# 4_RK3588_GND.net
KiCad netlist of a schematic drawn in Altium Designer
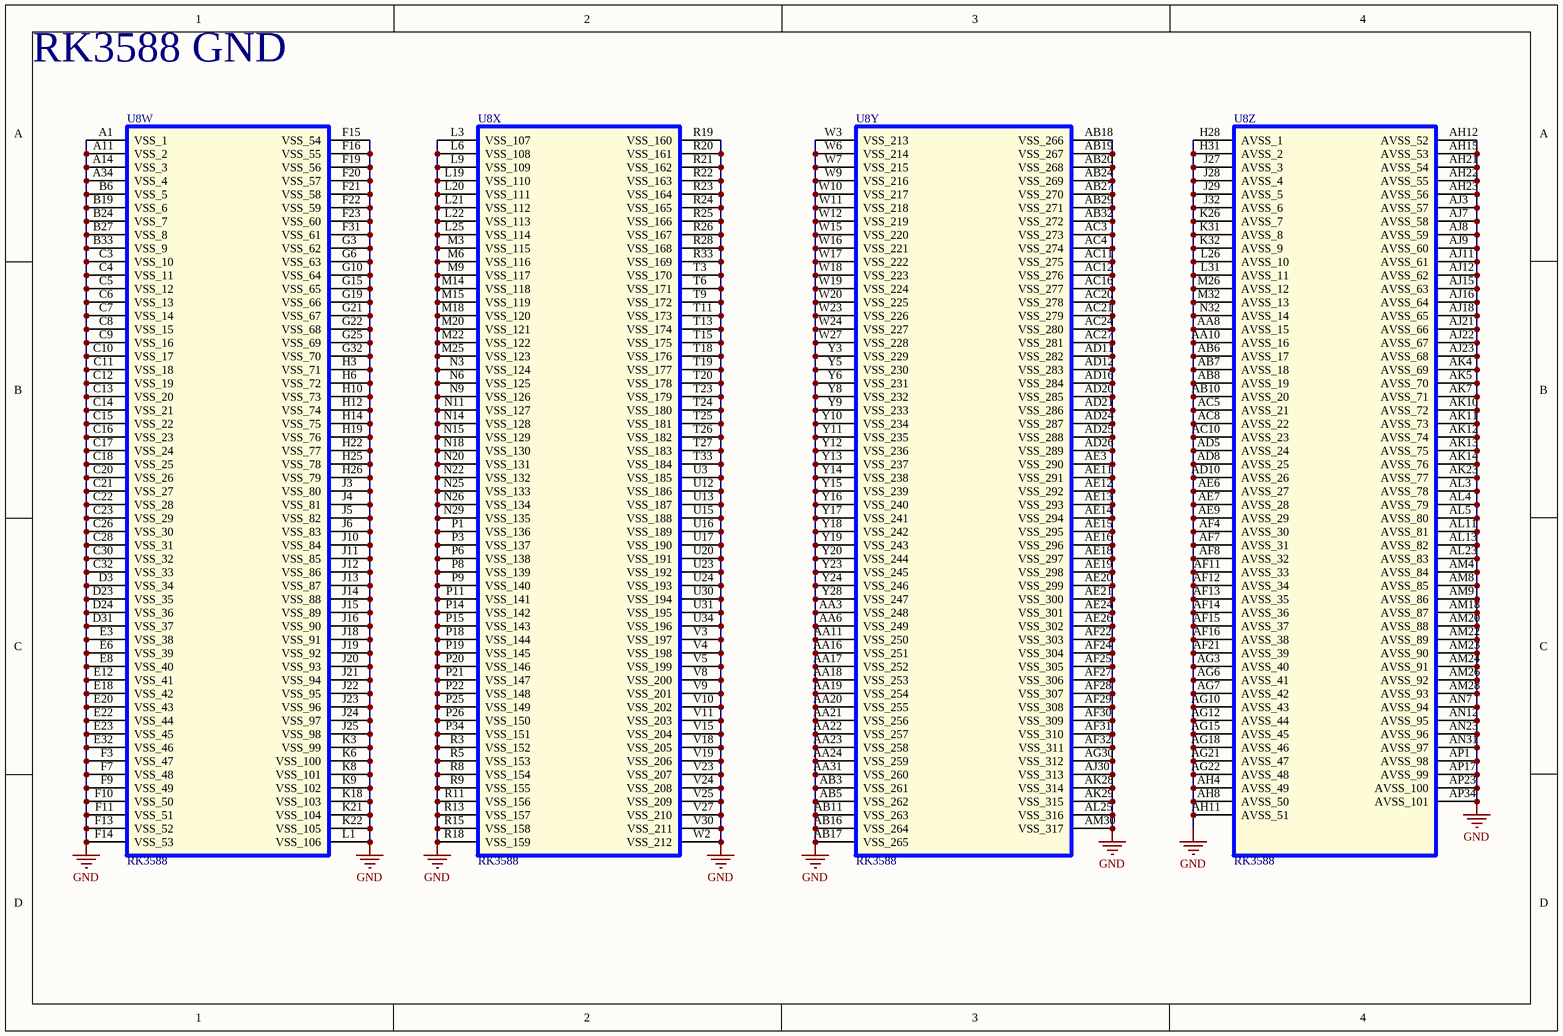
[diagram p0: 4.RK3588_GND.SchDoc]

(export (version "E")
  (design (tool "Eeschema 10.0.6"))
  (components
    (comp (ref "U8")
      (value "RK3588")
      (footprint "0.PCB1:BGA1088_23R00X23R00X2R00")
      (description "ROCKCHIP SOC")
      (libsource (lib "RK3588") (part "SOC_RK3588"))
    )
  )
  (nets
    (net (code "1") (name "GND") (class "Default")
      (node (ref "U8") (pin "A1") (pinfunction "VSS_1_A1") (pintype "power_in"))
      (node (ref "U8") (pin "A11") (pinfunction "VSS_2_A11") (pintype "power_in"))
      (node (ref "U8") (pin "A14") (pinfunction "VSS_3_A14") (pintype "power_in"))
      (node (ref "U8") (pin "A34") (pinfunction "VSS_4_A34") (pintype "power_in"))
      (node (ref "U8") (pin "AA10") (pinfunction "AVSS_16_AA10") (pintype "power_in"))
      (node (ref "U8") (pin "AA11") (pinfunction "VSS_250_AA11") (pintype "power_in"))
      (node (ref "U8") (pin "AA16") (pinfunction "VSS_251_AA16") (pintype "power_in"))
      (node (ref "U8") (pin "AA17") (pinfunction "VSS_252_AA17") (pintype "power_in"))
      (node (ref "U8") (pin "AA18") (pinfunction "VSS_253_AA18") (pintype "power_in"))
      (node (ref "U8") (pin "AA19") (pinfunction "VSS_254_AA19") (pintype "power_in"))
      (node (ref "U8") (pin "AA20") (pinfunction "VSS_255_AA20") (pintype "power_in"))
      (node (ref "U8") (pin "AA21") (pinfunction "VSS_256_AA21") (pintype "power_in"))
      (node (ref "U8") (pin "AA22") (pinfunction "VSS_257_AA22") (pintype "power_in"))
      (node (ref "U8") (pin "AA23") (pinfunction "VSS_258_AA23") (pintype "power_in"))
      (node (ref "U8") (pin "AA24") (pinfunction "VSS_259_AA24") (pintype "power_in"))
      (node (ref "U8") (pin "AA3") (pinfunction "VSS_248_AA3") (pintype "power_in"))
      (node (ref "U8") (pin "AA31") (pinfunction "VSS_260_AA31") (pintype "power_in"))
      (node (ref "U8") (pin "AA6") (pinfunction "VSS_249_AA6") (pintype "power_in"))
      (node (ref "U8") (pin "AA8") (pinfunction "AVSS_15_AA8") (pintype "power_in"))
      (node (ref "U8") (pin "AB10") (pinfunction "AVSS_20_AB10") (pintype "power_in"))
      (node (ref "U8") (pin "AB11") (pinfunction "VSS_263_AB11") (pintype "power_in"))
      (node (ref "U8") (pin "AB16") (pinfunction "VSS_264_AB16") (pintype "power_in"))
      (node (ref "U8") (pin "AB17") (pinfunction "VSS_265_AB17") (pintype "power_in"))
      (node (ref "U8") (pin "AB18") (pinfunction "VSS_266_AB18") (pintype "power_in"))
      (node (ref "U8") (pin "AB19") (pinfunction "VSS_267_AB19") (pintype "power_in"))
      (node (ref "U8") (pin "AB20") (pinfunction "VSS_268_AB20") (pintype "power_in"))
      (node (ref "U8") (pin "AB24") (pinfunction "VSS_269_AB24") (pintype "power_in"))
      (node (ref "U8") (pin "AB27") (pinfunction "VSS_270_AB27") (pintype "power_in"))
      (node (ref "U8") (pin "AB29") (pinfunction "VSS_271_AB29") (pintype "power_in"))
      (node (ref "U8") (pin "AB3") (pinfunction "VSS_261_AB3") (pintype "power_in"))
      (node (ref "U8") (pin "AB32") (pinfunction "VSS_272_AB32") (pintype "power_in"))
      (node (ref "U8") (pin "AB5") (pinfunction "VSS_262_AB5") (pintype "power_in"))
      (node (ref "U8") (pin "AB6") (pinfunction "AVSS_17_AB6") (pintype "power_in"))
      (node (ref "U8") (pin "AB7") (pinfunction "AVSS_18_AB7") (pintype "power_in"))
      (node (ref "U8") (pin "AB8") (pinfunction "AVSS_19_AB8") (pintype "power_in"))
      (node (ref "U8") (pin "AC10") (pinfunction "AVSS_23_AC10") (pintype "power_in"))
      (node (ref "U8") (pin "AC11") (pinfunction "VSS_275_AC11") (pintype "power_in"))
      (node (ref "U8") (pin "AC12") (pinfunction "VSS_276_AC12") (pintype "power_in"))
      (node (ref "U8") (pin "AC16") (pinfunction "VSS_277_AC16") (pintype "power_in"))
      (node (ref "U8") (pin "AC20") (pinfunction "VSS_278_AC20") (pintype "power_in"))
      (node (ref "U8") (pin "AC21") (pinfunction "VSS_279_AC21") (pintype "power_in"))
      (node (ref "U8") (pin "AC24") (pinfunction "VSS_280_AC24") (pintype "power_in"))
      (node (ref "U8") (pin "AC27") (pinfunction "VSS_281_AC27") (pintype "power_in"))
      (node (ref "U8") (pin "AC3") (pinfunction "VSS_273_AC3") (pintype "power_in"))
      (node (ref "U8") (pin "AC4") (pinfunction "VSS_274_AC4") (pintype "power_in"))
      (node (ref "U8") (pin "AC5") (pinfunction "AVSS_21_AC5") (pintype "power_in"))
      (node (ref "U8") (pin "AC8") (pinfunction "AVSS_22_AC8") (pintype "power_in"))
      (node (ref "U8") (pin "AD10") (pinfunction "AVSS_26_AD10") (pintype "power_in"))
      (node (ref "U8") (pin "AD11") (pinfunction "VSS_282_AD11") (pintype "power_in"))
      (node (ref "U8") (pin "AD12") (pinfunction "VSS_283_AD12") (pintype "power_in"))
      (node (ref "U8") (pin "AD16") (pinfunction "VSS_284_AD16") (pintype "power_in"))
      (node (ref "U8") (pin "AD20") (pinfunction "VSS_285_AD20") (pintype "power_in"))
      (node (ref "U8") (pin "AD21") (pinfunction "VSS_286_AD21") (pintype "power_in"))
      (node (ref "U8") (pin "AD24") (pinfunction "VSS_287_AD24") (pintype "power_in"))
      (node (ref "U8") (pin "AD25") (pinfunction "VSS_288_AD25") (pintype "power_in"))
      (node (ref "U8") (pin "AD26") (pinfunction "VSS_289_AD26") (pintype "power_in"))
      (node (ref "U8") (pin "AD5") (pinfunction "AVSS_24_AD5") (pintype "power_in"))
      (node (ref "U8") (pin "AD8") (pinfunction "AVSS_25_AD8") (pintype "power_in"))
      (node (ref "U8") (pin "AE11") (pinfunction "VSS_291_AE11") (pintype "power_in"))
      (node (ref "U8") (pin "AE12") (pinfunction "VSS_292_AE12") (pintype "power_in"))
      (node (ref "U8") (pin "AE13") (pinfunction "VSS_293_AE13") (pintype "power_in"))
      (node (ref "U8") (pin "AE14") (pinfunction "VSS_294_AE14") (pintype "power_in"))
      (node (ref "U8") (pin "AE15") (pinfunction "VSS_295_AE15") (pintype "power_in"))
      (node (ref "U8") (pin "AE16") (pinfunction "VSS_296_AE16") (pintype "power_in"))
      (node (ref "U8") (pin "AE18") (pinfunction "VSS_297_AE18") (pintype "power_in"))
      (node (ref "U8") (pin "AE19") (pinfunction "VSS_298_AE19") (pintype "power_in"))
      (node (ref "U8") (pin "AE20") (pinfunction "VSS_299_AE20") (pintype "power_in"))
      (node (ref "U8") (pin "AE21") (pinfunction "VSS_300_AE21") (pintype "power_in"))
      (node (ref "U8") (pin "AE24") (pinfunction "VSS_301_AE24") (pintype "power_in"))
      (node (ref "U8") (pin "AE26") (pinfunction "VSS_302_AE26") (pintype "power_in"))
      (node (ref "U8") (pin "AE3") (pinfunction "VSS_290_AE3") (pintype "power_in"))
      (node (ref "U8") (pin "AE6") (pinfunction "AVSS_27_AE6") (pintype "power_in"))
      (node (ref "U8") (pin "AE7") (pinfunction "AVSS_28_AE7") (pintype "power_in"))
      (node (ref "U8") (pin "AE9") (pinfunction "AVSS_29_AE9") (pintype "power_in"))
      (node (ref "U8") (pin "AF11") (pinfunction "AVSS_33_AF11") (pintype "power_in"))
      (node (ref "U8") (pin "AF12") (pinfunction "AVSS_34_AF12") (pintype "power_in"))
      (node (ref "U8") (pin "AF13") (pinfunction "AVSS_35_AF13") (pintype "power_in"))
      (node (ref "U8") (pin "AF14") (pinfunction "AVSS_36_AF14") (pintype "power_in"))
      (node (ref "U8") (pin "AF15") (pinfunction "AVSS_37_AF15") (pintype "power_in"))
      (node (ref "U8") (pin "AF16") (pinfunction "AVSS_38_AF16") (pintype "power_in"))
      (node (ref "U8") (pin "AF21") (pinfunction "AVSS_39_AF21") (pintype "power_in"))
      (node (ref "U8") (pin "AF22") (pinfunction "VSS_303_AF22") (pintype "power_in"))
      (node (ref "U8") (pin "AF24") (pinfunction "VSS_304_AF24") (pintype "power_in"))
      (node (ref "U8") (pin "AF25") (pinfunction "VSS_305_AF25") (pintype "power_in"))
      (node (ref "U8") (pin "AF27") (pinfunction "VSS_306_AF27") (pintype "power_in"))
      (node (ref "U8") (pin "AF28") (pinfunction "VSS_307_AF28") (pintype "power_in"))
      (node (ref "U8") (pin "AF29") (pinfunction "VSS_308_AF29") (pintype "power_in"))
      (node (ref "U8") (pin "AF30") (pinfunction "VSS_309_AF30") (pintype "power_in"))
      (node (ref "U8") (pin "AF31") (pinfunction "VSS_310_AF31") (pintype "power_in"))
      (node (ref "U8") (pin "AF32") (pinfunction "VSS_311_AF32") (pintype "power_in"))
      (node (ref "U8") (pin "AF4") (pinfunction "AVSS_30_AF4") (pintype "power_in"))
      (node (ref "U8") (pin "AF7") (pinfunction "AVSS_31_AF7") (pintype "power_in"))
      (node (ref "U8") (pin "AF8") (pinfunction "AVSS_32_AF8") (pintype "power_in"))
      (node (ref "U8") (pin "AG10") (pinfunction "AVSS_43_AG10") (pintype "power_in"))
      (node (ref "U8") (pin "AG12") (pinfunction "AVSS_44_AG12") (pintype "power_in"))
      (node (ref "U8") (pin "AG15") (pinfunction "AVSS_45_AG15") (pintype "power_in"))
      (node (ref "U8") (pin "AG18") (pinfunction "AVSS_46_AG18") (pintype "power_in"))
      (node (ref "U8") (pin "AG21") (pinfunction "AVSS_47_AG21") (pintype "power_in"))
      (node (ref "U8") (pin "AG22") (pinfunction "AVSS_48_AG22") (pintype "power_in"))
      (node (ref "U8") (pin "AG3") (pinfunction "AVSS_40_AG3") (pintype "power_in"))
      (node (ref "U8") (pin "AG30") (pinfunction "VSS_312_AG30") (pintype "power_in"))
      (node (ref "U8") (pin "AG6") (pinfunction "AVSS_41_AG6") (pintype "power_in"))
      (node (ref "U8") (pin "AG7") (pinfunction "AVSS_42_AG7") (pintype "power_in"))
      (node (ref "U8") (pin "AH11") (pinfunction "AVSS_51_AH11") (pintype "power_in"))
      (node (ref "U8") (pin "AH12") (pinfunction "AVSS_52_AH12") (pintype "power_in"))
      (node (ref "U8") (pin "AH15") (pinfunction "AVSS_53_AH15") (pintype "power_in"))
      (node (ref "U8") (pin "AH21") (pinfunction "AVSS_54_AH21") (pintype "power_in"))
      (node (ref "U8") (pin "AH22") (pinfunction "AVSS_55_AH22") (pintype "power_in"))
      (node (ref "U8") (pin "AH23") (pinfunction "AVSS_56_AH23") (pintype "power_in"))
      (node (ref "U8") (pin "AH4") (pinfunction "AVSS_49_AH4") (pintype "power_in"))
      (node (ref "U8") (pin "AH8") (pinfunction "AVSS_50_AH8") (pintype "power_in"))
      (node (ref "U8") (pin "AJ11") (pinfunction "AVSS_61_AJ11") (pintype "power_in"))
      (node (ref "U8") (pin "AJ12") (pinfunction "AVSS_62_AJ12") (pintype "power_in"))
      (node (ref "U8") (pin "AJ15") (pinfunction "AVSS_63_AJ15") (pintype "power_in"))
      (node (ref "U8") (pin "AJ16") (pinfunction "AVSS_64_AJ16") (pintype "power_in"))
      (node (ref "U8") (pin "AJ18") (pinfunction "AVSS_65_AJ18") (pintype "power_in"))
      (node (ref "U8") (pin "AJ21") (pinfunction "AVSS_66_AJ21") (pintype "power_in"))
      (node (ref "U8") (pin "AJ22") (pinfunction "AVSS_67_AJ22") (pintype "power_in"))
      (node (ref "U8") (pin "AJ23") (pinfunction "AVSS_68_AJ23") (pintype "power_in"))
      (node (ref "U8") (pin "AJ3") (pinfunction "AVSS_57_AJ3") (pintype "power_in"))
      (node (ref "U8") (pin "AJ30") (pinfunction "VSS_313_AJ30") (pintype "power_in"))
      (node (ref "U8") (pin "AJ7") (pinfunction "AVSS_58_AJ7") (pintype "power_in"))
      (node (ref "U8") (pin "AJ8") (pinfunction "AVSS_59_AJ8") (pintype "power_in"))
      (node (ref "U8") (pin "AJ9") (pinfunction "AVSS_60_AJ9") (pintype "power_in"))
      (node (ref "U8") (pin "AK10") (pinfunction "AVSS_72_AK10") (pintype "power_in"))
      (node (ref "U8") (pin "AK11") (pinfunction "AVSS_73_AK11") (pintype "power_in"))
      (node (ref "U8") (pin "AK12") (pinfunction "AVSS_74_AK12") (pintype "power_in"))
      (node (ref "U8") (pin "AK13") (pinfunction "AVSS_75_AK13") (pintype "power_in"))
      (node (ref "U8") (pin "AK14") (pinfunction "AVSS_76_AK14") (pintype "power_in"))
      (node (ref "U8") (pin "AK23") (pinfunction "AVSS_77_AK23") (pintype "power_in"))
      (node (ref "U8") (pin "AK28") (pinfunction "VSS_314_AK28") (pintype "power_in"))
      (node (ref "U8") (pin "AK29") (pinfunction "VSS_315_AK29") (pintype "power_in"))
      (node (ref "U8") (pin "AK4") (pinfunction "AVSS_69_AK4") (pintype "power_in"))
      (node (ref "U8") (pin "AK5") (pinfunction "AVSS_70_AK5") (pintype "power_in"))
      (node (ref "U8") (pin "AK7") (pinfunction "AVSS_71_AK7") (pintype "power_in"))
      (node (ref "U8") (pin "AL11") (pinfunction "AVSS_81_AL11") (pintype "power_in"))
      (node (ref "U8") (pin "AL13") (pinfunction "AVSS_82_AL13") (pintype "power_in"))
      (node (ref "U8") (pin "AL23") (pinfunction "AVSS_83_AL23") (pintype "power_in"))
      (node (ref "U8") (pin "AL25") (pinfunction "VSS_316_AL25") (pintype "power_in"))
      (node (ref "U8") (pin "AL3") (pinfunction "AVSS_78_AL3") (pintype "power_in"))
      (node (ref "U8") (pin "AL4") (pinfunction "AVSS_79_AL4") (pintype "power_in"))
      (node (ref "U8") (pin "AL5") (pinfunction "AVSS_80_AL5") (pintype "power_in"))
      (node (ref "U8") (pin "AM18") (pinfunction "AVSS_87_AM18") (pintype "power_in"))
      (node (ref "U8") (pin "AM20") (pinfunction "AVSS_88_AM20") (pintype "power_in"))
      (node (ref "U8") (pin "AM22") (pinfunction "AVSS_89_AM22") (pintype "power_in"))
      (node (ref "U8") (pin "AM23") (pinfunction "AVSS_90_AM23") (pintype "power_in"))
      (node (ref "U8") (pin "AM24") (pinfunction "AVSS_91_AM24") (pintype "power_in"))
      (node (ref "U8") (pin "AM26") (pinfunction "AVSS_92_AM26") (pintype "power_in"))
      (node (ref "U8") (pin "AM28") (pinfunction "AVSS_93_AM28") (pintype "power_in"))
      (node (ref "U8") (pin "AM30") (pinfunction "VSS_317_AM30") (pintype "power_in"))
      (node (ref "U8") (pin "AM4") (pinfunction "AVSS_84_AM4") (pintype "power_in"))
      (node (ref "U8") (pin "AM8") (pinfunction "AVSS_85_AM8") (pintype "power_in"))
      (node (ref "U8") (pin "AM9") (pinfunction "AVSS_86_AM9") (pintype "power_in"))
      (node (ref "U8") (pin "AN12") (pinfunction "AVSS_95_AN12") (pintype "power_in"))
      (node (ref "U8") (pin "AN23") (pinfunction "AVSS_96_AN23") (pintype "power_in"))
      (node (ref "U8") (pin "AN31") (pinfunction "AVSS_97_AN31") (pintype "power_in"))
      (node (ref "U8") (pin "AN7") (pinfunction "AVSS_94_AN7") (pintype "power_in"))
      (node (ref "U8") (pin "AP1") (pinfunction "AVSS_98_AP1") (pintype "power_in"))
      (node (ref "U8") (pin "AP17") (pinfunction "AVSS_99_AP17") (pintype "power_in"))
      (node (ref "U8") (pin "AP23") (pinfunction "AVSS_100_AP23") (pintype "passive"))
      (node (ref "U8") (pin "AP34") (pinfunction "AVSS_101_AP34") (pintype "power_in"))
      (node (ref "U8") (pin "B19") (pinfunction "VSS_6_B19") (pintype "power_in"))
      (node (ref "U8") (pin "B24") (pinfunction "VSS_7_B24") (pintype "power_in"))
      (node (ref "U8") (pin "B27") (pinfunction "VSS_8_B27") (pintype "power_in"))
      (node (ref "U8") (pin "B33") (pinfunction "VSS_9_B33") (pintype "power_in"))
      (node (ref "U8") (pin "B6") (pinfunction "VSS_5_B6") (pintype "power_in"))
      (node (ref "U8") (pin "C10") (pinfunction "VSS_17_C10") (pintype "power_in"))
      (node (ref "U8") (pin "C11") (pinfunction "VSS_18_C11") (pintype "power_in"))
      (node (ref "U8") (pin "C12") (pinfunction "VSS_19_C12") (pintype "power_in"))
      (node (ref "U8") (pin "C13") (pinfunction "VSS_20_C13") (pintype "power_in"))
      (node (ref "U8") (pin "C14") (pinfunction "VSS_21_C14") (pintype "power_in"))
      (node (ref "U8") (pin "C15") (pinfunction "VSS_22_C15") (pintype "power_in"))
      (node (ref "U8") (pin "C16") (pinfunction "VSS_23_C16") (pintype "power_in"))
      (node (ref "U8") (pin "C17") (pinfunction "VSS_24_C17") (pintype "power_in"))
      (node (ref "U8") (pin "C18") (pinfunction "VSS_25_C18") (pintype "power_in"))
      (node (ref "U8") (pin "C20") (pinfunction "VSS_26_C20") (pintype "power_in"))
      (node (ref "U8") (pin "C21") (pinfunction "VSS_27_C21") (pintype "power_in"))
      (node (ref "U8") (pin "C22") (pinfunction "VSS_28_C22") (pintype "power_in"))
      (node (ref "U8") (pin "C23") (pinfunction "VSS_29_C23") (pintype "power_in"))
      (node (ref "U8") (pin "C26") (pinfunction "VSS_30_C26") (pintype "power_in"))
      (node (ref "U8") (pin "C28") (pinfunction "VSS_31_C28") (pintype "power_in"))
      (node (ref "U8") (pin "C3") (pinfunction "VSS_10_C3") (pintype "power_in"))
      (node (ref "U8") (pin "C30") (pinfunction "VSS_32_C30") (pintype "power_in"))
      (node (ref "U8") (pin "C32") (pinfunction "VSS_33_C32") (pintype "power_in"))
      (node (ref "U8") (pin "C4") (pinfunction "VSS_11_C4") (pintype "power_in"))
      (node (ref "U8") (pin "C5") (pinfunction "VSS_12_C5") (pintype "power_in"))
      (node (ref "U8") (pin "C6") (pinfunction "VSS_13_C6") (pintype "power_in"))
      (node (ref "U8") (pin "C7") (pinfunction "VSS_14_C7") (pintype "power_in"))
      (node (ref "U8") (pin "C8") (pinfunction "VSS_15_C8") (pintype "power_in"))
      (node (ref "U8") (pin "C9") (pinfunction "VSS_16_C9") (pintype "power_in"))
      (node (ref "U8") (pin "D23") (pinfunction "VSS_35_D23") (pintype "power_in"))
      (node (ref "U8") (pin "D24") (pinfunction "VSS_36_D24") (pintype "power_in"))
      (node (ref "U8") (pin "D3") (pinfunction "VSS_34_D3") (pintype "power_in"))
      (node (ref "U8") (pin "D31") (pinfunction "VSS_37_D31") (pintype "power_in"))
      (node (ref "U8") (pin "E12") (pinfunction "VSS_41_E12") (pintype "power_in"))
      (node (ref "U8") (pin "E18") (pinfunction "VSS_42_E18") (pintype "power_in"))
      (node (ref "U8") (pin "E20") (pinfunction "VSS_43_E20") (pintype "power_in"))
      (node (ref "U8") (pin "E22") (pinfunction "VSS_44_E22") (pintype "power_in"))
      (node (ref "U8") (pin "E23") (pinfunction "VSS_45_E23") (pintype "power_in"))
      (node (ref "U8") (pin "E3") (pinfunction "VSS_38_E3") (pintype "power_in"))
      (node (ref "U8") (pin "E32") (pinfunction "VSS_46_E32") (pintype "power_in"))
      (node (ref "U8") (pin "E6") (pinfunction "VSS_39_E6") (pintype "power_in"))
      (node (ref "U8") (pin "E8") (pinfunction "VSS_40_E8") (pintype "power_in"))
      (node (ref "U8") (pin "F10") (pinfunction "VSS_50_F10") (pintype "power_in"))
      (node (ref "U8") (pin "F11") (pinfunction "VSS_51_F11") (pintype "power_in"))
      (node (ref "U8") (pin "F13") (pinfunction "VSS_52_F13") (pintype "power_in"))
      (node (ref "U8") (pin "F14") (pinfunction "VSS_53_F14") (pintype "power_in"))
      (node (ref "U8") (pin "F15") (pinfunction "VSS_54_F15") (pintype "power_in"))
      (node (ref "U8") (pin "F16") (pinfunction "VSS_55_F16") (pintype "power_in"))
      (node (ref "U8") (pin "F19") (pinfunction "VSS_56_F19") (pintype "power_in"))
      (node (ref "U8") (pin "F20") (pinfunction "VSS_57_F20") (pintype "power_in"))
      (node (ref "U8") (pin "F21") (pinfunction "VSS_58_F21") (pintype "power_in"))
      (node (ref "U8") (pin "F22") (pinfunction "VSS_59_F22") (pintype "power_in"))
      (node (ref "U8") (pin "F23") (pinfunction "VSS_60_F23") (pintype "power_in"))
      (node (ref "U8") (pin "F3") (pinfunction "VSS_47_F3") (pintype "power_in"))
      (node (ref "U8") (pin "F31") (pinfunction "VSS_61_F31") (pintype "power_in"))
      (node (ref "U8") (pin "F7") (pinfunction "VSS_48_F7") (pintype "power_in"))
      (node (ref "U8") (pin "F9") (pinfunction "VSS_49_F9") (pintype "power_in"))
      (node (ref "U8") (pin "G10") (pinfunction "VSS_64_G10") (pintype "power_in"))
      (node (ref "U8") (pin "G15") (pinfunction "VSS_65_G15") (pintype "power_in"))
      (node (ref "U8") (pin "G19") (pinfunction "VSS_66_G19") (pintype "power_in"))
      (node (ref "U8") (pin "G21") (pinfunction "VSS_67_G21") (pintype "power_in"))
      (node (ref "U8") (pin "G22") (pinfunction "VSS_68_G22") (pintype "power_in"))
      (node (ref "U8") (pin "G25") (pinfunction "VSS_69_G25") (pintype "power_in"))
      (node (ref "U8") (pin "G3") (pinfunction "VSS_62_G3") (pintype "power_in"))
      (node (ref "U8") (pin "G32") (pinfunction "VSS_70_G32") (pintype "power_in"))
      (node (ref "U8") (pin "G6") (pinfunction "VSS_63_G6") (pintype "power_in"))
      (node (ref "U8") (pin "H10") (pinfunction "VSS_73_H10") (pintype "power_in"))
      (node (ref "U8") (pin "H12") (pinfunction "VSS_74_H12") (pintype "power_in"))
      (node (ref "U8") (pin "H14") (pinfunction "VSS_75_H14") (pintype "power_in"))
      (node (ref "U8") (pin "H19") (pinfunction "VSS_76_H19") (pintype "power_in"))
      (node (ref "U8") (pin "H22") (pinfunction "VSS_77_H22") (pintype "power_in"))
      (node (ref "U8") (pin "H25") (pinfunction "VSS_78_H25") (pintype "power_in"))
      (node (ref "U8") (pin "H26") (pinfunction "VSS_79_H26") (pintype "power_in"))
      (node (ref "U8") (pin "H28") (pinfunction "AVSS_1_H28") (pintype "power_in"))
      (node (ref "U8") (pin "H3") (pinfunction "VSS_71_H3") (pintype "power_in"))
      (node (ref "U8") (pin "H31") (pinfunction "AVSS_2_H31") (pintype "power_in"))
      (node (ref "U8") (pin "H6") (pinfunction "VSS_72_H6") (pintype "power_in"))
      (node (ref "U8") (pin "J10") (pinfunction "VSS_84_J10") (pintype "power_in"))
      (node (ref "U8") (pin "J11") (pinfunction "VSS_85_J11") (pintype "power_in"))
      (node (ref "U8") (pin "J12") (pinfunction "VSS_86_J12") (pintype "power_in"))
      (node (ref "U8") (pin "J13") (pinfunction "VSS_87_J13") (pintype "power_in"))
      (node (ref "U8") (pin "J14") (pinfunction "VSS_88_J14") (pintype "power_in"))
      (node (ref "U8") (pin "J15") (pinfunction "VSS_89_J15") (pintype "power_in"))
      (node (ref "U8") (pin "J16") (pinfunction "VSS_90_J16") (pintype "power_in"))
      (node (ref "U8") (pin "J18") (pinfunction "VSS_91_J18") (pintype "power_in"))
      (node (ref "U8") (pin "J19") (pinfunction "VSS_92_J19") (pintype "power_in"))
      (node (ref "U8") (pin "J20") (pinfunction "VSS_93_J20") (pintype "power_in"))
      (node (ref "U8") (pin "J21") (pinfunction "VSS_94_J21") (pintype "power_in"))
      (node (ref "U8") (pin "J22") (pinfunction "VSS_95_J22") (pintype "power_in"))
      (node (ref "U8") (pin "J23") (pinfunction "VSS_96_J23") (pintype "power_in"))
      (node (ref "U8") (pin "J24") (pinfunction "VSS_97_J24") (pintype "power_in"))
      (node (ref "U8") (pin "J25") (pinfunction "VSS_98_J25") (pintype "power_in"))
      (node (ref "U8") (pin "J27") (pinfunction "AVSS_3_J27") (pintype "power_in"))
      (node (ref "U8") (pin "J28") (pinfunction "AVSS_4_J28") (pintype "power_in"))
      (node (ref "U8") (pin "J29") (pinfunction "AVSS_5_J29") (pintype "power_in"))
      (node (ref "U8") (pin "J3") (pinfunction "VSS_80_J3") (pintype "power_in"))
      (node (ref "U8") (pin "J32") (pinfunction "AVSS_6_J32") (pintype "power_in"))
      (node (ref "U8") (pin "J4") (pinfunction "VSS_81_J4") (pintype "power_in"))
      (node (ref "U8") (pin "J5") (pinfunction "VSS_82_J5") (pintype "power_in"))
      (node (ref "U8") (pin "J6") (pinfunction "VSS_83_J6") (pintype "power_in"))
      (node (ref "U8") (pin "K18") (pinfunction "VSS_103_K18") (pintype "power_in"))
      (node (ref "U8") (pin "K21") (pinfunction "VSS_104_K21") (pintype "power_in"))
      (node (ref "U8") (pin "K22") (pinfunction "VSS_105_K22") (pintype "power_in"))
      (node (ref "U8") (pin "K26") (pinfunction "AVSS_7_K26") (pintype "power_in"))
      (node (ref "U8") (pin "K3") (pinfunction "VSS_99_K3") (pintype "power_in"))
      (node (ref "U8") (pin "K31") (pinfunction "AVSS_8_K31") (pintype "power_in"))
      (node (ref "U8") (pin "K32") (pinfunction "AVSS_9_K32") (pintype "power_in"))
      (node (ref "U8") (pin "K6") (pinfunction "VSS_100_K6") (pintype "power_in"))
      (node (ref "U8") (pin "K8") (pinfunction "VSS_101_K8") (pintype "power_in"))
      (node (ref "U8") (pin "K9") (pinfunction "VSS_102_K9") (pintype "power_in"))
      (node (ref "U8") (pin "L1") (pinfunction "VSS_106_L1") (pintype "power_in"))
      (node (ref "U8") (pin "L19") (pinfunction "VSS_110_L19") (pintype "power_in"))
      (node (ref "U8") (pin "L20") (pinfunction "VSS_111_L20") (pintype "power_in"))
      (node (ref "U8") (pin "L21") (pinfunction "VSS_112_L21") (pintype "power_in"))
      (node (ref "U8") (pin "L22") (pinfunction "VSS_113_L22") (pintype "power_in"))
      (node (ref "U8") (pin "L25") (pinfunction "VSS_114_L25") (pintype "power_in"))
      (node (ref "U8") (pin "L26") (pinfunction "AVSS_10_L26") (pintype "power_in"))
      (node (ref "U8") (pin "L3") (pinfunction "VSS_107_L3") (pintype "power_in"))
      (node (ref "U8") (pin "L31") (pinfunction "AVSS_11_L31") (pintype "power_in"))
      (node (ref "U8") (pin "L6") (pinfunction "VSS_108_L6") (pintype "power_in"))
      (node (ref "U8") (pin "L9") (pinfunction "VSS_109_L9") (pintype "power_in"))
      (node (ref "U8") (pin "M14") (pinfunction "VSS_118_M14") (pintype "power_in"))
      (node (ref "U8") (pin "M15") (pinfunction "VSS_119_M15") (pintype "power_in"))
      (node (ref "U8") (pin "M18") (pinfunction "VSS_120_M18") (pintype "power_in"))
      (node (ref "U8") (pin "M20") (pinfunction "VSS_121_M20") (pintype "power_in"))
      (node (ref "U8") (pin "M22") (pinfunction "VSS_122_M22") (pintype "power_in"))
      (node (ref "U8") (pin "M25") (pinfunction "VSS_123_M25") (pintype "power_in"))
      (node (ref "U8") (pin "M26") (pinfunction "AVSS_12_M26") (pintype "power_in"))
      (node (ref "U8") (pin "M3") (pinfunction "VSS_115_M3") (pintype "power_in"))
      (node (ref "U8") (pin "M32") (pinfunction "AVSS_13_M32") (pintype "power_in"))
      (node (ref "U8") (pin "M6") (pinfunction "VSS_116_M6") (pintype "power_in"))
      (node (ref "U8") (pin "M9") (pinfunction "VSS_117_M9") (pintype "power_in"))
      (node (ref "U8") (pin "N11") (pinfunction "VSS_127_N11") (pintype "power_in"))
      (node (ref "U8") (pin "N14") (pinfunction "VSS_128_N14") (pintype "power_in"))
      (node (ref "U8") (pin "N15") (pinfunction "VSS_129_N15") (pintype "power_in"))
      (node (ref "U8") (pin "N18") (pinfunction "VSS_130_N18") (pintype "power_in"))
      (node (ref "U8") (pin "N20") (pinfunction "VSS_131_N20") (pintype "power_in"))
      (node (ref "U8") (pin "N22") (pinfunction "VSS_132_N22") (pintype "power_in"))
      (node (ref "U8") (pin "N25") (pinfunction "VSS_133_N25") (pintype "power_in"))
      (node (ref "U8") (pin "N26") (pinfunction "VSS_134_N26") (pintype "power_in"))
      (node (ref "U8") (pin "N29") (pinfunction "VSS_135_N29") (pintype "power_in"))
      (node (ref "U8") (pin "N3") (pinfunction "VSS_124_N3") (pintype "power_in"))
      (node (ref "U8") (pin "N32") (pinfunction "AVSS_14_N32") (pintype "power_in"))
      (node (ref "U8") (pin "N6") (pinfunction "VSS_125_N6") (pintype "power_in"))
      (node (ref "U8") (pin "N9") (pinfunction "VSS_126_N9") (pintype "power_in"))
      (node (ref "U8") (pin "P1") (pinfunction "VSS_136_P1") (pintype "power_in"))
      (node (ref "U8") (pin "P11") (pinfunction "VSS_141_P11") (pintype "power_in"))
      (node (ref "U8") (pin "P14") (pinfunction "VSS_142_P14") (pintype "power_in"))
      (node (ref "U8") (pin "P15") (pinfunction "VSS_143_P15") (pintype "power_in"))
      (node (ref "U8") (pin "P18") (pinfunction "VSS_144_P18") (pintype "power_in"))
      (node (ref "U8") (pin "P19") (pinfunction "VSS_145_P19") (pintype "power_in"))
      (node (ref "U8") (pin "P20") (pinfunction "VSS_146_P20") (pintype "power_in"))
      (node (ref "U8") (pin "P21") (pinfunction "VSS_147_P21") (pintype "power_in"))
      (node (ref "U8") (pin "P22") (pinfunction "VSS_148_P22") (pintype "power_in"))
      (node (ref "U8") (pin "P25") (pinfunction "VSS_149_P25") (pintype "power_in"))
      (node (ref "U8") (pin "P26") (pinfunction "VSS_150_P26") (pintype "power_in"))
      (node (ref "U8") (pin "P3") (pinfunction "VSS_137_P3") (pintype "power_in"))
      (node (ref "U8") (pin "P34") (pinfunction "VSS_151_P34") (pintype "power_in"))
      (node (ref "U8") (pin "P6") (pinfunction "VSS_138_P6") (pintype "power_in"))
      (node (ref "U8") (pin "P8") (pinfunction "VSS_139_P8") (pintype "power_in"))
      (node (ref "U8") (pin "P9") (pinfunction "VSS_140_P9") (pintype "power_in"))
      (node (ref "U8") (pin "R11") (pinfunction "VSS_156_R11") (pintype "power_in"))
      (node (ref "U8") (pin "R13") (pinfunction "VSS_157_R13") (pintype "power_in"))
      (node (ref "U8") (pin "R15") (pinfunction "VSS_158_R15") (pintype "power_in"))
      (node (ref "U8") (pin "R18") (pinfunction "VSS_159_R18") (pintype "power_in"))
      (node (ref "U8") (pin "R19") (pinfunction "VSS_160_R19") (pintype "power_in"))
      (node (ref "U8") (pin "R20") (pinfunction "VSS_161_R20") (pintype "power_in"))
      (node (ref "U8") (pin "R21") (pinfunction "VSS_162_R21") (pintype "power_in"))
      (node (ref "U8") (pin "R22") (pinfunction "VSS_163_R22") (pintype "power_in"))
      (node (ref "U8") (pin "R23") (pinfunction "VSS_164_R23") (pintype "power_in"))
      (node (ref "U8") (pin "R24") (pinfunction "VSS_165_R24") (pintype "power_in"))
      (node (ref "U8") (pin "R25") (pinfunction "VSS_166_R25") (pintype "power_in"))
      (node (ref "U8") (pin "R26") (pinfunction "VSS_167_R26") (pintype "power_in"))
      (node (ref "U8") (pin "R28") (pinfunction "VSS_168_R28") (pintype "power_in"))
      (node (ref "U8") (pin "R3") (pinfunction "VSS_152_R3") (pintype "power_in"))
      (node (ref "U8") (pin "R33") (pinfunction "VSS_169_R33") (pintype "power_in"))
      (node (ref "U8") (pin "R5") (pinfunction "VSS_153_R5") (pintype "power_in"))
      (node (ref "U8") (pin "R8") (pinfunction "VSS_154_R8") (pintype "power_in"))
      (node (ref "U8") (pin "R9") (pinfunction "VSS_155_R9") (pintype "power_in"))
      (node (ref "U8") (pin "T11") (pinfunction "VSS_173_T11") (pintype "power_in"))
      (node (ref "U8") (pin "T13") (pinfunction "VSS_174_T13") (pintype "power_in"))
      (node (ref "U8") (pin "T15") (pinfunction "VSS_175_T15") (pintype "power_in"))
      (node (ref "U8") (pin "T18") (pinfunction "VSS_176_T18") (pintype "power_in"))
      (node (ref "U8") (pin "T19") (pinfunction "VSS_177_T19") (pintype "power_in"))
      (node (ref "U8") (pin "T20") (pinfunction "VSS_178_T20") (pintype "power_in"))
      (node (ref "U8") (pin "T23") (pinfunction "VSS_179_T23") (pintype "power_in"))
      (node (ref "U8") (pin "T24") (pinfunction "VSS_180_T24") (pintype "power_in"))
      (node (ref "U8") (pin "T25") (pinfunction "VSS_181_T25") (pintype "power_in"))
      (node (ref "U8") (pin "T26") (pinfunction "VSS_182_T26") (pintype "power_in"))
      (node (ref "U8") (pin "T27") (pinfunction "VSS_183_T27") (pintype "power_in"))
      (node (ref "U8") (pin "T3") (pinfunction "VSS_170_T3") (pintype "power_in"))
      (node (ref "U8") (pin "T33") (pinfunction "VSS_184_T33") (pintype "power_in"))
      (node (ref "U8") (pin "T6") (pinfunction "VSS_171_T6") (pintype "power_in"))
      (node (ref "U8") (pin "T9") (pinfunction "VSS_172_T9") (pintype "power_in"))
      (node (ref "U8") (pin "U12") (pinfunction "VSS_186_U12") (pintype "power_in"))
      (node (ref "U8") (pin "U13") (pinfunction "VSS_187_U13") (pintype "power_in"))
      (node (ref "U8") (pin "U15") (pinfunction "VSS_188_U15") (pintype "power_in"))
      (node (ref "U8") (pin "U16") (pinfunction "VSS_189_U16") (pintype "power_in"))
      (node (ref "U8") (pin "U17") (pinfunction "VSS_190_U17") (pintype "power_in"))
      (node (ref "U8") (pin "U20") (pinfunction "VSS_191_U20") (pintype "power_in"))
      (node (ref "U8") (pin "U23") (pinfunction "VSS_192_U23") (pintype "power_in"))
      (node (ref "U8") (pin "U24") (pinfunction "VSS_193_U24") (pintype "power_in"))
      (node (ref "U8") (pin "U3") (pinfunction "VSS_185_U3") (pintype "power_in"))
      (node (ref "U8") (pin "U30") (pinfunction "VSS_194_U30") (pintype "power_in"))
      (node (ref "U8") (pin "U31") (pinfunction "VSS_195_U31") (pintype "power_in"))
      (node (ref "U8") (pin "U34") (pinfunction "VSS_196_U34") (pintype "power_in"))
      (node (ref "U8") (pin "V10") (pinfunction "VSS_202_V10") (pintype "power_in"))
      (node (ref "U8") (pin "V11") (pinfunction "VSS_203_V11") (pintype "power_in"))
      (node (ref "U8") (pin "V15") (pinfunction "VSS_204_V15") (pintype "power_in"))
      (node (ref "U8") (pin "V18") (pinfunction "VSS_205_V18") (pintype "power_in"))
      (node (ref "U8") (pin "V19") (pinfunction "VSS_206_V19") (pintype "power_in"))
      (node (ref "U8") (pin "V23") (pinfunction "VSS_207_V23") (pintype "power_in"))
      (node (ref "U8") (pin "V24") (pinfunction "VSS_208_V24") (pintype "power_in"))
      (node (ref "U8") (pin "V25") (pinfunction "VSS_209_V25") (pintype "power_in"))
      (node (ref "U8") (pin "V27") (pinfunction "VSS_210_V27") (pintype "power_in"))
      (node (ref "U8") (pin "V3") (pinfunction "VSS_197_V3") (pintype "power_in"))
      (node (ref "U8") (pin "V30") (pinfunction "VSS_211_V30") (pintype "power_in"))
      (node (ref "U8") (pin "V4") (pinfunction "VSS_198_V4") (pintype "power_in"))
      (node (ref "U8") (pin "V5") (pinfunction "VSS_199_V5") (pintype "power_in"))
      (node (ref "U8") (pin "V8") (pinfunction "VSS_200_V8") (pintype "power_in"))
      (node (ref "U8") (pin "V9") (pinfunction "VSS_201_V9") (pintype "power_in"))
      (node (ref "U8") (pin "W10") (pinfunction "VSS_217_W10") (pintype "power_in"))
      (node (ref "U8") (pin "W11") (pinfunction "VSS_218_W11") (pintype "power_in"))
      (node (ref "U8") (pin "W12") (pinfunction "VSS_219_W12") (pintype "power_in"))
      (node (ref "U8") (pin "W15") (pinfunction "VSS_220_W15") (pintype "power_in"))
      (node (ref "U8") (pin "W16") (pinfunction "VSS_221_W16") (pintype "power_in"))
      (node (ref "U8") (pin "W17") (pinfunction "VSS_222_W17") (pintype "power_in"))
      (node (ref "U8") (pin "W18") (pinfunction "VSS_223_W18") (pintype "power_in"))
      (node (ref "U8") (pin "W19") (pinfunction "VSS_224_W19") (pintype "power_in"))
      (node (ref "U8") (pin "W2") (pinfunction "VSS_212_W2") (pintype "power_in"))
      (node (ref "U8") (pin "W20") (pinfunction "VSS_225_W20") (pintype "power_in"))
      (node (ref "U8") (pin "W23") (pinfunction "VSS_226_W23") (pintype "power_in"))
      (node (ref "U8") (pin "W24") (pinfunction "VSS_227_W24") (pintype "power_in"))
      (node (ref "U8") (pin "W27") (pinfunction "VSS_228_W27") (pintype "power_in"))
      (node (ref "U8") (pin "W3") (pinfunction "VSS_213_W3") (pintype "power_in"))
      (node (ref "U8") (pin "W6") (pinfunction "VSS_214_W6") (pintype "power_in"))
      (node (ref "U8") (pin "W7") (pinfunction "VSS_215_W7") (pintype "power_in"))
      (node (ref "U8") (pin "W9") (pinfunction "VSS_216_W9") (pintype "power_in"))
      (node (ref "U8") (pin "Y10") (pinfunction "VSS_234_Y10") (pintype "power_in"))
      (node (ref "U8") (pin "Y11") (pinfunction "VSS_235_Y11") (pintype "power_in"))
      (node (ref "U8") (pin "Y12") (pinfunction "VSS_236_Y12") (pintype "power_in"))
      (node (ref "U8") (pin "Y13") (pinfunction "VSS_237_Y13") (pintype "power_in"))
      (node (ref "U8") (pin "Y14") (pinfunction "VSS_238_Y14") (pintype "power_in"))
      (node (ref "U8") (pin "Y15") (pinfunction "VSS_239_Y15") (pintype "power_in"))
      (node (ref "U8") (pin "Y16") (pinfunction "VSS_240_Y16") (pintype "power_in"))
      (node (ref "U8") (pin "Y17") (pinfunction "VSS_241_Y17") (pintype "power_in"))
      (node (ref "U8") (pin "Y18") (pinfunction "VSS_242_Y18") (pintype "power_in"))
      (node (ref "U8") (pin "Y19") (pinfunction "VSS_243_Y19") (pintype "power_in"))
      (node (ref "U8") (pin "Y20") (pinfunction "VSS_244_Y20") (pintype "power_in"))
      (node (ref "U8") (pin "Y23") (pinfunction "VSS_245_Y23") (pintype "power_in"))
      (node (ref "U8") (pin "Y24") (pinfunction "VSS_246_Y24") (pintype "power_in"))
      (node (ref "U8") (pin "Y28") (pinfunction "VSS_247_Y28") (pintype "power_in"))
      (node (ref "U8") (pin "Y3") (pinfunction "VSS_229_Y3") (pintype "power_in"))
      (node (ref "U8") (pin "Y5") (pinfunction "VSS_230_Y5") (pintype "power_in"))
      (node (ref "U8") (pin "Y6") (pinfunction "VSS_231_Y6") (pintype "power_in"))
      (node (ref "U8") (pin "Y8") (pinfunction "VSS_232_Y8") (pintype "power_in"))
      (node (ref "U8") (pin "Y9") (pinfunction "VSS_233_Y9") (pintype "power_in"))
    )
  )
)
